# Control_Stage.net
KiCad netlist of a schematic drawn in Altium Designer
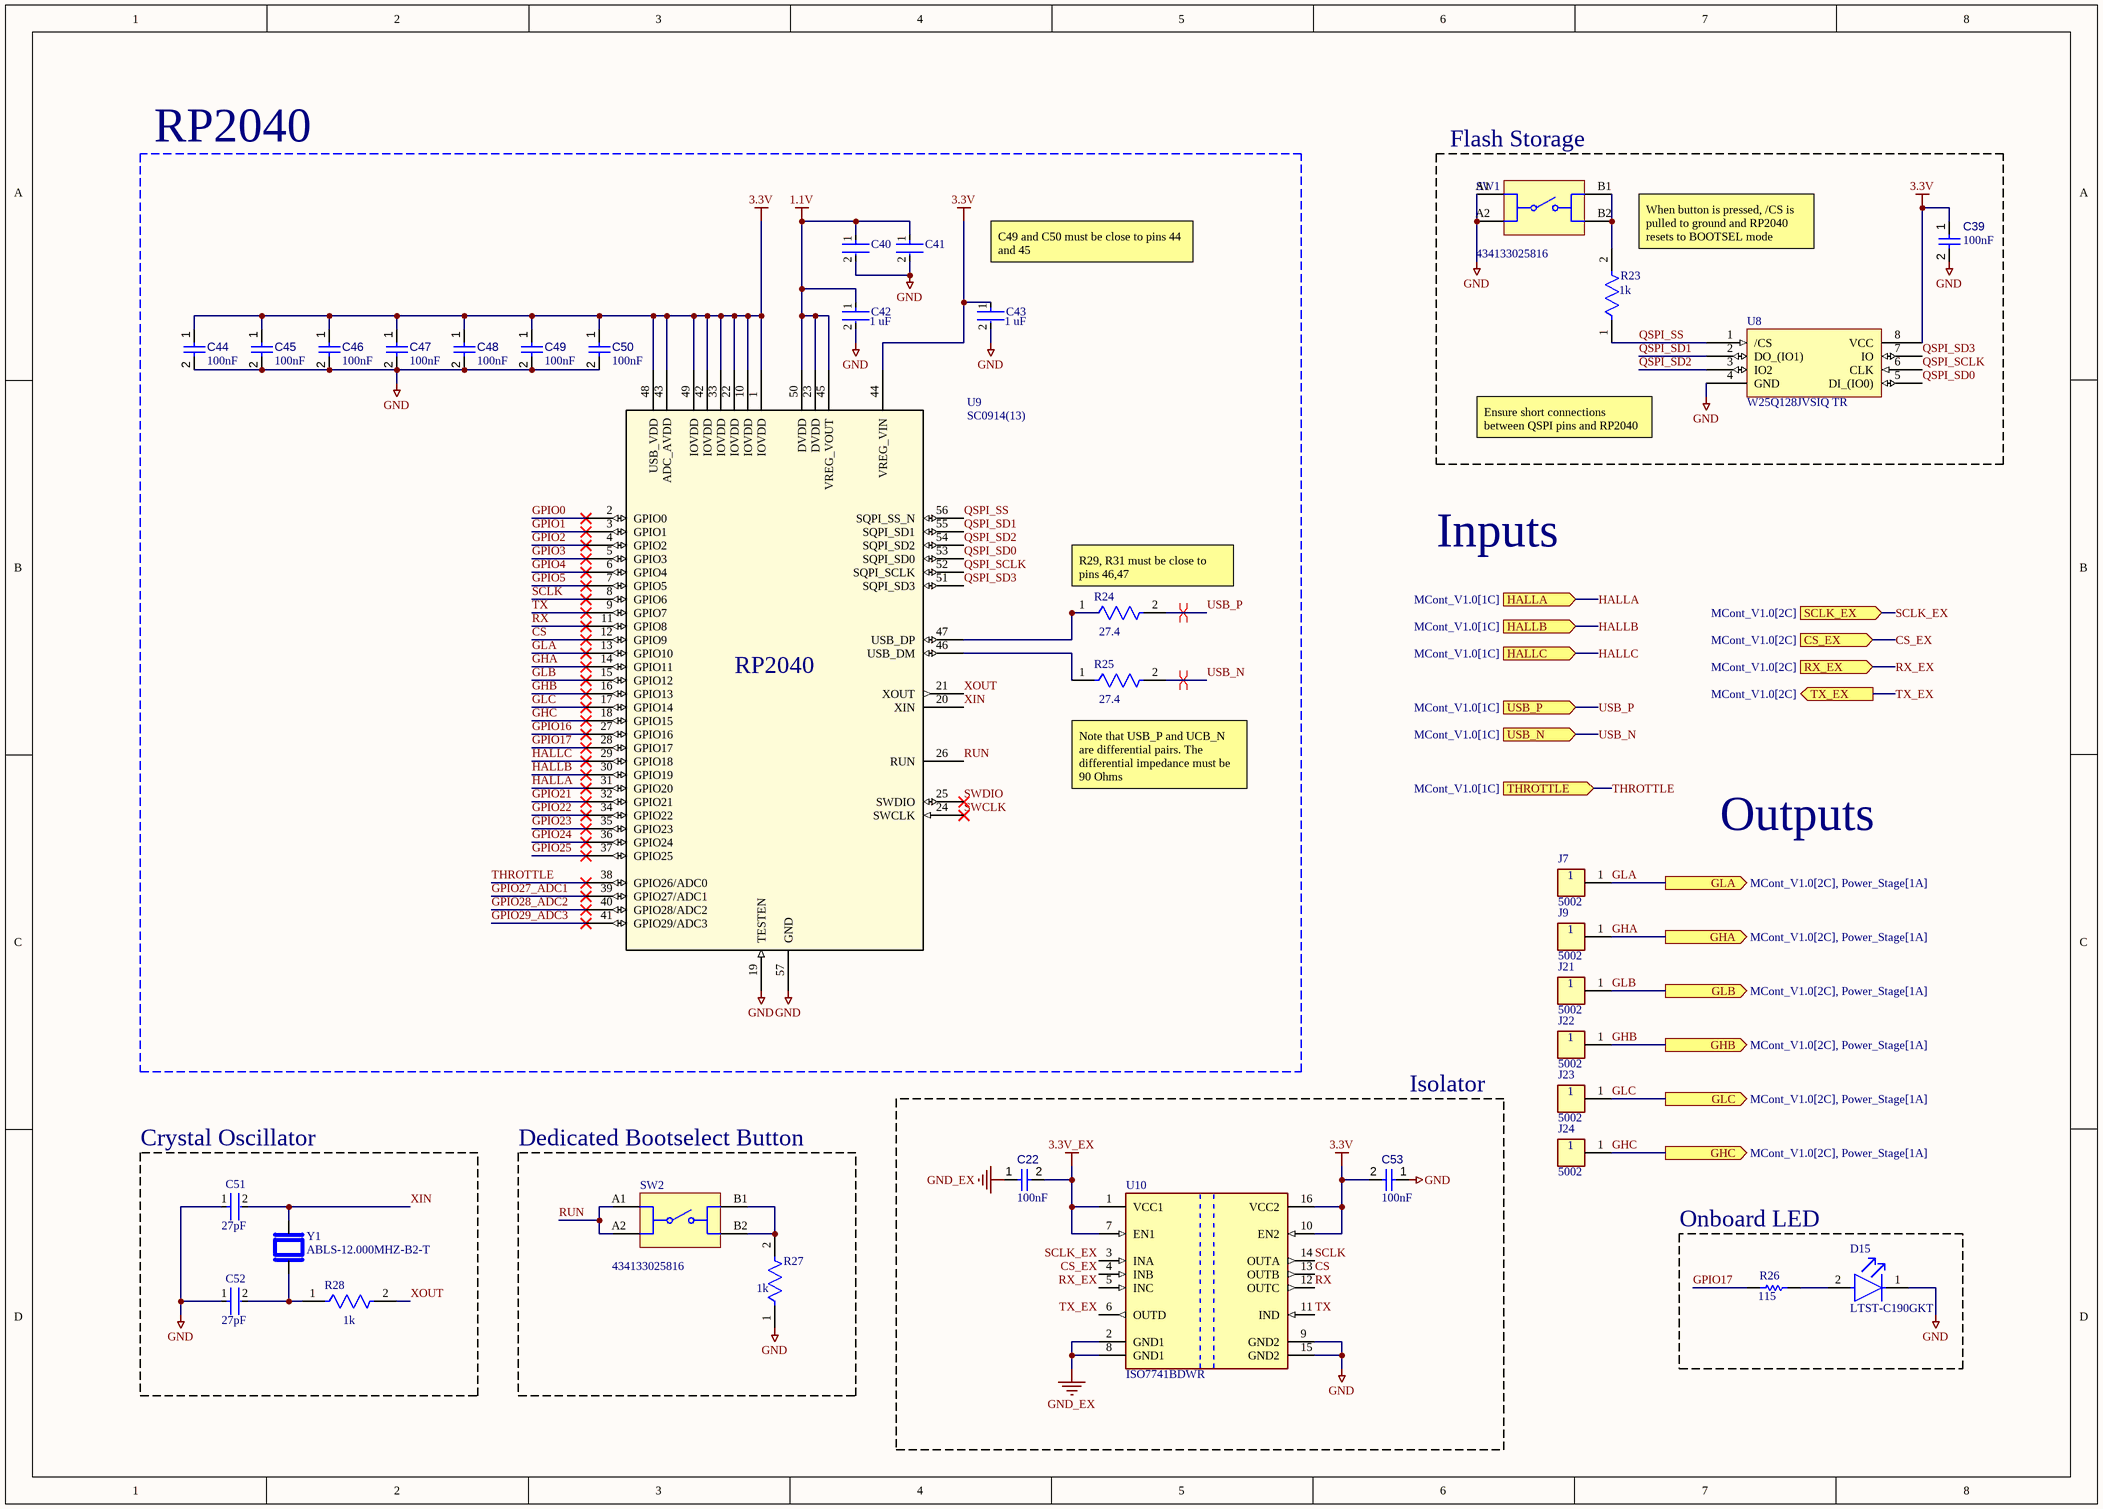
[diagram p0: Control_Stage.SchDoc]

(export (version "E")
  (design (tool "Eeschema 10.0.6"))
  (components
    (comp (ref "C22")
      (value "100nF")
      (footprint "FP-CL10-IPC_B")
      (fields (field (name "Comment") "CL10B104KC8NNNC"))
      (libsource (lib "CEV Electrical") (part "CAP-NP-2"))
    )
    (comp (ref "C39")
      (value "100nF")
      (footprint "FP-CL10-IPC_B")
      (fields (field (name "Comment") "CL10B104KC8NNNC"))
      (libsource (lib "CEV Electrical") (part "CAP-NP-2"))
    )
    (comp (ref "C40")
      (value "CL10B104KC8NNNC")
      (footprint "FP-CL10-IPC_A")
      (description "Cap Ceramic 100nF 100V X7R ±10% Pad SMD 0603 +125°C T/R")
      (fields (field (name "TOLERANCE") "10%"))
      (libsource (lib "Altium Content Vault") (part "b4654b650e69147ec39a6b967a45e02"))
    )
    (comp (ref "C41")
      (value "CL10B104KC8NNNC")
      (footprint "FP-CL10-IPC_A")
      (description "Cap Ceramic 100nF 100V X7R ±10% Pad SMD 0603 +125°C T/R")
      (fields (field (name "TOLERANCE") "10%"))
      (libsource (lib "Altium Content Vault") (part "b4654b650e69147ec39a6b967a45e02"))
    )
    (comp (ref "C42")
      (value "UMK107AB7105KA-T")
      (footprint "FP-0603-L_1_6_0_15-W_0_8-IPC_C")
      (description "Ceramic Capacitor General Use 1uF ±10% 50V X7R 0603")
      (fields (field (name "TOLERANCE") "10%"))
      (libsource (lib "Altium Content Vault") (part "11868f565c42a9108669ba33697ecf6"))
    )
    (comp (ref "C43")
      (value "UMK107AB7105KA-T")
      (footprint "FP-0603-L_1_6_0_15-W_0_8-IPC_C")
      (description "Ceramic Capacitor General Use 1uF ±10% 50V X7R 0603")
      (fields (field (name "TOLERANCE") "10%"))
      (libsource (lib "Altium Content Vault") (part "11868f565c42a9108669ba33697ecf6"))
    )
    (comp (ref "C44")
      (value "100nF")
      (footprint "FP-CL10-IPC_B")
      (fields (field (name "Comment") "CL10B104KC8NNNC"))
      (libsource (lib "CEV Electrical") (part "CAP-NP-2"))
    )
    (comp (ref "C45")
      (value "100nF")
      (footprint "FP-CL10-IPC_B")
      (fields (field (name "Comment") "CL10B104KC8NNNC"))
      (libsource (lib "CEV Electrical") (part "CAP-NP-2"))
    )
    (comp (ref "C46")
      (value "100nF")
      (footprint "FP-CL10-IPC_B")
      (fields (field (name "Comment") "CL10B104KC8NNNC"))
      (libsource (lib "CEV Electrical") (part "CAP-NP-2"))
    )
    (comp (ref "C47")
      (value "100nF")
      (footprint "FP-CL10-IPC_B")
      (fields (field (name "Comment") "CL10B104KC8NNNC"))
      (libsource (lib "CEV Electrical") (part "CAP-NP-2"))
    )
    (comp (ref "C48")
      (value "100nF")
      (footprint "FP-CL10-IPC_B")
      (fields (field (name "Comment") "CL10B104KC8NNNC"))
      (libsource (lib "CEV Electrical") (part "CAP-NP-2"))
    )
    (comp (ref "C49")
      (value "100nF")
      (footprint "FP-CL10-IPC_B")
      (fields (field (name "Comment") "CL10B104KC8NNNC"))
      (libsource (lib "CEV Electrical") (part "CAP-NP-2"))
    )
    (comp (ref "C50")
      (value "100nF")
      (footprint "FP-CL10-IPC_B")
      (fields (field (name "Comment") "CL10B104KC8NNNC"))
      (libsource (lib "CEV Electrical") (part "CAP-NP-2"))
    )
    (comp (ref "C51")
      (value "C0603C270J5GACTU")
      (footprint "FP-C0603C-CF-MFG")
      (description "CAP CER 27PF 50V C0G/NP0 0603")
      (fields
        (field (name "TOLERANCE") "0.05")
        (field (name "OCTOPART") "https://octopart.com/c0603c270j5gactu-kemet-136059")
      )
      (libsource (lib "Altium Content Vault") (part "b4654b650e69147ec39a6b967a45e02"))
    )
    (comp (ref "C52")
      (value "C0603C270J5GACTU")
      (footprint "FP-C0603C-CF-MFG")
      (description "CAP CER 27PF 50V C0G/NP0 0603")
      (fields
        (field (name "TOLERANCE") "0.05")
        (field (name "OCTOPART") "https://octopart.com/c0603c270j5gactu-kemet-136059")
      )
      (libsource (lib "Altium Content Vault") (part "b4654b650e69147ec39a6b967a45e02"))
    )
    (comp (ref "C53")
      (value "100nF")
      (footprint "FP-CL10-IPC_B")
      (fields (field (name "Comment") "CL10B104KC8NNNC"))
      (libsource (lib "CEV Electrical") (part "CAP-NP-2"))
    )
    (comp (ref "D15")
      (value "LTST-C190GKT")
      (footprint "FP-LTST-C190GKT-MFG")
      (description "LED GREEN CLEAR CHIP SMD")
      (fields (field (name "VOLTAGE") "2V"))
      (libsource (lib "Altium Content Vault") (part "8706943c75ba83719d021d2fdc84c58"))
    )
    (comp (ref "J7")
      (value "5002")
      (footprint "FP-5002-MFG")
      (description "PC TEST POINT MINIATURE WHITE")
      (libsource (lib "Altium Content Vault") (part "1e4615820a309e3ce90f9e6d957b7fa"))
    )
    (comp (ref "J9")
      (value "5002")
      (footprint "FP-5002-MFG")
      (description "PC TEST POINT MINIATURE WHITE")
      (libsource (lib "Altium Content Vault") (part "1e4615820a309e3ce90f9e6d957b7fa"))
    )
    (comp (ref "J21")
      (value "5002")
      (footprint "FP-5002-MFG")
      (description "PC TEST POINT MINIATURE WHITE")
      (libsource (lib "Altium Content Vault") (part "1e4615820a309e3ce90f9e6d957b7fa"))
    )
    (comp (ref "J22")
      (value "5002")
      (footprint "FP-5002-MFG")
      (description "PC TEST POINT MINIATURE WHITE")
      (libsource (lib "Altium Content Vault") (part "1e4615820a309e3ce90f9e6d957b7fa"))
    )
    (comp (ref "J23")
      (value "5002")
      (footprint "FP-5002-MFG")
      (description "PC TEST POINT MINIATURE WHITE")
      (libsource (lib "Altium Content Vault") (part "1e4615820a309e3ce90f9e6d957b7fa"))
    )
    (comp (ref "J24")
      (value "5002")
      (footprint "FP-5002-MFG")
      (description "PC TEST POINT MINIATURE WHITE")
      (libsource (lib "Altium Content Vault") (part "1e4615820a309e3ce90f9e6d957b7fa"))
    )
    (comp (ref "R23")
      (value "RC0603FR-071KL")
      (footprint "FP-RC0603-0_55-IPC_C")
      (description "RES 1K OHM 1% 1/10W 0603")
      (fields (field (name "TOLERANCE") "1%"))
      (libsource (lib "Altium Content Vault") (part "1029c3af85768c4190bb7ad29bc67b5"))
    )
    (comp (ref "R24")
      (value "CRCW060327R4FKEA")
      (footprint "FP-CRCW0603-e3-MFG")
      (description "RES Thick Film, 27.4Ω, 1%, 0.1W, 100ppm/°C, 0603")
      (fields (field (name "TOLERANCE") "1%"))
      (libsource (lib "Altium Content Vault") (part "1029c3af85768c4190bb7ad29bc67b5"))
    )
    (comp (ref "R25")
      (value "CRCW060327R4FKEA")
      (footprint "FP-CRCW0603-e3-MFG")
      (description "RES Thick Film, 27.4Ω, 1%, 0.1W, 100ppm/°C, 0603")
      (fields (field (name "TOLERANCE") "1%"))
      (libsource (lib "Altium Content Vault") (part "1029c3af85768c4190bb7ad29bc67b5"))
    )
    (comp (ref "R26")
      (value "ERJ-3EKF1150V")
      (footprint "RESC1608X55X30NL15T15")
      (fields (field (name "MANUFACTURER") "Panasonic"))
      (libsource (lib "Altium Content Vault") (part "RES"))
    )
    (comp (ref "R27")
      (value "RC0603FR-071KL")
      (footprint "FP-RC0603-0_55-IPC_C")
      (description "RES 1K OHM 1% 1/10W 0603")
      (fields (field (name "TOLERANCE") "1%"))
      (libsource (lib "Altium Content Vault") (part "1029c3af85768c4190bb7ad29bc67b5"))
    )
    (comp (ref "R28")
      (value "RC0603FR-071KL")
      (footprint "FP-RC0603-0_55-IPC_C")
      (description "RES 1K OHM 1% 1/10W 0603")
      (fields (field (name "TOLERANCE") "1%"))
      (libsource (lib "Altium Content Vault") (part "1029c3af85768c4190bb7ad29bc67b5"))
    )
    (comp (ref "SW1")
      (value "434133025816")
      (footprint "434133025816")
      (description "Tactile Switch, 0.05A, 16Vdc, 160Gf, Smd Rohs Compliant: Yes")
      (libsource (lib "Altium Content Vault") (part "SPST-NO_4P"))
    )
    (comp (ref "SW2")
      (value "434133025816")
      (footprint "434133025816")
      (description "Tactile Switch, 0.05A, 16Vdc, 160Gf, Smd Rohs Compliant: Yes")
      (libsource (lib "Altium Content Vault") (part "SPST-NO_4P"))
    )
    (comp (ref "U8")
      (value "W25Q128JVSIQ TR")
      (footprint "W25Q128JVSIQ TR-Footprint-1")
      (description "NOR Flash Serial (SPI, Dual SPI, Quad SPI) 3V/3.3V 128M-bit 16M x 8 6ns 8-Pin SOIC T/R")
      (libsource (lib "CEV Electrical New") (part "W25Q128JVSIQ TR-Symbol-1"))
    )
    (comp (ref "U9")
      (value "SC0914(13)")
      (footprint "SC0914(13)-Footprint-1")
      (description "RISC Microcontroller, FLASH, Cortex-M0+ CPU, 133MHz, CMOS")
      (libsource (lib "CEV Electrical New") (part "SC0914(13)-Symbol-1"))
    )
    (comp (ref "U10")
      (value "ISO7741BDWR")
      (footprint "FP-DW0016A-IPC_A")
      (description "DIG ISO - MYNA - QUAD")
      (libsource (lib "Altium Content Vault") (part "66022d5b456763423f468824eb3e28a"))
    )
    (comp (ref "Y1")
      (value "ABLS-12.000MHZ-B2-T")
      (footprint "XTAL_ABLS-12.000MHZ-B2-T")
      (description "Crystal 12MHz ±20ppm (Tol) ±50ppm (Stability) 18pF FUND 50Ohm 2-Pin HC-49/US SMD T/R")
      (fields (field (name "TOLERANCE") "0.002%"))
      (libsource (lib "CEV Electrical New") (part "ABLS-12.000MHZ-B2-T"))
    )
  )
  (nets
    (net (code "1") (name "/CS") (class "Default")
      (node (ref "U10") (pin "13") (pinfunction "OUTB_13") (pintype "output"))
      (node (ref "U9") (pin "12") (pinfunction "GPIO9_12") (pintype "bidirectional"))
    )
    (net (code "2") (name "/CS_EX") (class "Default")
      (node (ref "U10") (pin "4") (pinfunction "INB_4") (pintype "input"))
    )
    (net (code "3") (name "/GHA") (class "Default")
      (node (ref "J9") (pin "1") (pinfunction "1_1") (pintype "passive"))
      (node (ref "U9") (pin "14") (pinfunction "GPIO11_14") (pintype "bidirectional"))
    )
    (net (code "4") (name "/GHB") (class "Default")
      (node (ref "J22") (pin "1") (pinfunction "1_1") (pintype "passive"))
      (node (ref "U9") (pin "16") (pinfunction "GPIO13_16") (pintype "bidirectional"))
    )
    (net (code "5") (name "/GHC") (class "Default")
      (node (ref "J24") (pin "1") (pinfunction "1_1") (pintype "passive"))
      (node (ref "U9") (pin "18") (pinfunction "GPIO15_18") (pintype "bidirectional"))
    )
    (net (code "6") (name "/GLA") (class "Default")
      (node (ref "J7") (pin "1") (pinfunction "1_1") (pintype "passive"))
      (node (ref "U9") (pin "13") (pinfunction "GPIO10_13") (pintype "bidirectional"))
    )
    (net (code "7") (name "/GLB") (class "Default")
      (node (ref "J21") (pin "1") (pinfunction "1_1") (pintype "passive"))
      (node (ref "U9") (pin "15") (pinfunction "GPIO12_15") (pintype "bidirectional"))
    )
    (net (code "8") (name "/GLC") (class "Default")
      (node (ref "J23") (pin "1") (pinfunction "1_1") (pintype "passive"))
      (node (ref "U9") (pin "17") (pinfunction "GPIO14_17") (pintype "bidirectional"))
    )
    (net (code "9") (name "/GPIO0") (class "Default")
      (node (ref "U9") (pin "2") (pinfunction "GPIO0_2") (pintype "bidirectional+no_connect"))
    )
    (net (code "10") (name "/GPIO1") (class "Default")
      (node (ref "U9") (pin "3") (pinfunction "GPIO1_3") (pintype "bidirectional+no_connect"))
    )
    (net (code "11") (name "/GPIO2") (class "Default")
      (node (ref "U9") (pin "4") (pinfunction "GPIO2_4") (pintype "bidirectional+no_connect"))
    )
    (net (code "12") (name "/GPIO3") (class "Default")
      (node (ref "U9") (pin "5") (pinfunction "GPIO3_5") (pintype "bidirectional+no_connect"))
    )
    (net (code "13") (name "/GPIO4") (class "Default")
      (node (ref "U9") (pin "6") (pinfunction "GPIO4_6") (pintype "bidirectional+no_connect"))
    )
    (net (code "14") (name "/GPIO5") (class "Default")
      (node (ref "U9") (pin "7") (pinfunction "GPIO5_7") (pintype "bidirectional+no_connect"))
    )
    (net (code "15") (name "/GPIO16") (class "Default")
      (node (ref "U9") (pin "27") (pinfunction "GPIO16_27") (pintype "bidirectional+no_connect"))
    )
    (net (code "16") (name "/GPIO17") (class "Default")
      (node (ref "R26") (pin "1") (pinfunction "1_1") (pintype "passive"))
      (node (ref "U9") (pin "28") (pinfunction "GPIO17_28") (pintype "bidirectional"))
    )
    (net (code "17") (name "/GPIO21") (class "Default")
      (node (ref "U9") (pin "32") (pinfunction "GPIO21_32") (pintype "bidirectional+no_connect"))
    )
    (net (code "18") (name "/GPIO22") (class "Default")
      (node (ref "U9") (pin "34") (pinfunction "GPIO22_34") (pintype "bidirectional+no_connect"))
    )
    (net (code "19") (name "/GPIO23") (class "Default")
      (node (ref "U9") (pin "35") (pinfunction "GPIO23_35") (pintype "bidirectional+no_connect"))
    )
    (net (code "20") (name "/GPIO24") (class "Default")
      (node (ref "U9") (pin "36") (pinfunction "GPIO24_36") (pintype "bidirectional+no_connect"))
    )
    (net (code "21") (name "/GPIO25") (class "Default")
      (node (ref "U9") (pin "37") (pinfunction "GPIO25_37") (pintype "bidirectional+no_connect"))
    )
    (net (code "22") (name "/GPIO27_ADC1") (class "Default")
      (node (ref "U9") (pin "39") (pinfunction "GPIO27/ADC1_39") (pintype "bidirectional+no_connect"))
    )
    (net (code "23") (name "/GPIO28_ADC2") (class "Default")
      (node (ref "U9") (pin "40") (pinfunction "GPIO28/ADC2_40") (pintype "bidirectional+no_connect"))
    )
    (net (code "24") (name "/GPIO29_ADC3") (class "Default")
      (node (ref "U9") (pin "41") (pinfunction "GPIO29/ADC3_41") (pintype "bidirectional+no_connect"))
    )
    (net (code "25") (name "/HALLA") (class "Default")
      (node (ref "U9") (pin "31") (pinfunction "GPIO20_31") (pintype "bidirectional+no_connect"))
    )
    (net (code "26") (name "/HALLB") (class "Default")
      (node (ref "U9") (pin "30") (pinfunction "GPIO19_30") (pintype "bidirectional+no_connect"))
    )
    (net (code "27") (name "/HALLC") (class "Default")
      (node (ref "U9") (pin "29") (pinfunction "GPIO18_29") (pintype "bidirectional+no_connect"))
    )
    (net (code "28") (name "/QSPI_SCLK") (class "Default")
      (node (ref "U8") (pin "6") (pinfunction "CLK_6") (pintype "input"))
      (node (ref "U9") (pin "52") (pinfunction "SQPI_SCLK_52") (pintype "bidirectional"))
    )
    (net (code "29") (name "/QSPI_SD0") (class "Default")
      (node (ref "U8") (pin "5") (pinfunction "DI_(IO0)_5") (pintype "bidirectional"))
      (node (ref "U9") (pin "53") (pinfunction "SQPI_SD0_53") (pintype "bidirectional"))
    )
    (net (code "30") (name "/QSPI_SD1") (class "Default")
      (node (ref "U8") (pin "2") (pinfunction "DO_(IO1)_2") (pintype "bidirectional"))
      (node (ref "U9") (pin "55") (pinfunction "SQPI_SD1_55") (pintype "bidirectional"))
    )
    (net (code "31") (name "/QSPI_SD2") (class "Default")
      (node (ref "U8") (pin "3") (pinfunction "IO2_3") (pintype "bidirectional"))
      (node (ref "U9") (pin "54") (pinfunction "SQPI_SD2_54") (pintype "bidirectional"))
    )
    (net (code "32") (name "/QSPI_SD3") (class "Default")
      (node (ref "U8") (pin "7") (pinfunction "IO_7") (pintype "bidirectional"))
      (node (ref "U9") (pin "51") (pinfunction "SQPI_SD3_51") (pintype "bidirectional"))
    )
    (net (code "33") (name "/QSPI_SS") (class "Default")
      (node (ref "R23") (pin "1") (pinfunction "1_1") (pintype "passive"))
      (node (ref "U8") (pin "1") (pinfunction "/CS_1") (pintype "input"))
      (node (ref "U9") (pin "56") (pinfunction "SQPI_SS_N_56") (pintype "bidirectional"))
    )
    (net (code "34") (name "/RUN") (class "Default")
      (node (ref "SW2") (pin "A1") (pinfunction "A1_A1") (pintype "passive"))
      (node (ref "SW2") (pin "A2") (pinfunction "A2_A2") (pintype "passive"))
      (node (ref "U9") (pin "26") (pinfunction "RUN_26") (pintype "passive"))
    )
    (net (code "35") (name "/RX") (class "Default")
      (node (ref "U10") (pin "12") (pinfunction "OUTC_12") (pintype "output"))
      (node (ref "U9") (pin "11") (pinfunction "GPIO8_11") (pintype "bidirectional"))
    )
    (net (code "36") (name "/RX_EX") (class "Default")
      (node (ref "U10") (pin "5") (pinfunction "INC_5") (pintype "input"))
    )
    (net (code "37") (name "/SCLK") (class "Default")
      (node (ref "U10") (pin "14") (pinfunction "OUTA_14") (pintype "output"))
      (node (ref "U9") (pin "8") (pinfunction "GPIO6_8") (pintype "bidirectional"))
    )
    (net (code "38") (name "/SCLK_EX") (class "Default")
      (node (ref "U10") (pin "3") (pinfunction "INA_3") (pintype "input"))
    )
    (net (code "39") (name "/SWCLK") (class "Default")
      (node (ref "U9") (pin "24") (pinfunction "SWCLK_24") (pintype "input+no_connect"))
    )
    (net (code "40") (name "/SWDIO") (class "Default")
      (node (ref "U9") (pin "25") (pinfunction "SWDIO_25") (pintype "bidirectional+no_connect"))
    )
    (net (code "41") (name "/THROTTLE") (class "Default")
      (node (ref "U9") (pin "38") (pinfunction "GPIO26/ADC0_38") (pintype "bidirectional"))
    )
    (net (code "42") (name "/TX") (class "Default")
      (node (ref "U10") (pin "11") (pinfunction "IND_11") (pintype "input"))
      (node (ref "U9") (pin "9") (pinfunction "GPIO7_9") (pintype "bidirectional"))
    )
    (net (code "43") (name "/TX_EX") (class "Default")
      (node (ref "U10") (pin "6") (pinfunction "OUTD_6") (pintype "output"))
    )
    (net (code "44") (name "/USB_N") (class "Default")
      (node (ref "R25") (pin "2") (pinfunction "2_2") (pintype "passive"))
    )
    (net (code "45") (name "/USB_P") (class "Default")
      (node (ref "R24") (pin "2") (pinfunction "2_2") (pintype "passive"))
    )
    (net (code "46") (name "/XIN") (class "Default")
      (node (ref "C51") (pin "2") (pinfunction "2_2") (pintype "passive"))
      (node (ref "U9") (pin "20") (pinfunction "XIN_20") (pintype "passive"))
      (node (ref "Y1") (pin "2") (pinfunction "2_2") (pintype "passive"))
    )
    (net (code "47") (name "/XOUT") (class "Default")
      (node (ref "R28") (pin "2") (pinfunction "2_2") (pintype "passive"))
      (node (ref "U9") (pin "21") (pinfunction "XOUT_21") (pintype "output"))
    )
    (net (code "48") (name "1.1V") (class "Default")
      (node (ref "C40") (pin "1") (pinfunction "1_1") (pintype "passive"))
      (node (ref "C41") (pin "1") (pinfunction "1_1") (pintype "passive"))
      (node (ref "C42") (pin "1") (pinfunction "1_1") (pintype "passive"))
      (node (ref "U9") (pin "23") (pinfunction "DVDD_23") (pintype "power_in"))
      (node (ref "U9") (pin "45") (pinfunction "VREG_VOUT_45") (pintype "power_in"))
      (node (ref "U9") (pin "50") (pinfunction "DVDD_50") (pintype "power_in"))
    )
    (net (code "49") (name "3.3V") (class "Default")
      (node (ref "C39") (pin "1") (pinfunction "1_1") (pintype "passive"))
      (node (ref "C43") (pin "1") (pinfunction "1_1") (pintype "passive"))
      (node (ref "C44") (pin "1") (pinfunction "1_1") (pintype "passive"))
      (node (ref "C45") (pin "1") (pinfunction "1_1") (pintype "passive"))
      (node (ref "C46") (pin "1") (pinfunction "1_1") (pintype "passive"))
      (node (ref "C47") (pin "1") (pinfunction "1_1") (pintype "passive"))
      (node (ref "C48") (pin "1") (pinfunction "1_1") (pintype "passive"))
      (node (ref "C49") (pin "1") (pinfunction "1_1") (pintype "passive"))
      (node (ref "C50") (pin "1") (pinfunction "1_1") (pintype "passive"))
      (node (ref "C53") (pin "2") (pinfunction "2_2") (pintype "passive"))
      (node (ref "U10") (pin "10") (pinfunction "EN2_10") (pintype "input"))
      (node (ref "U10") (pin "16") (pinfunction "VCC2_16") (pintype "power_in"))
      (node (ref "U8") (pin "8") (pinfunction "VCC_8") (pintype "power_in"))
      (node (ref "U9") (pin "1") (pinfunction "IOVDD_1") (pintype "power_in"))
      (node (ref "U9") (pin "10") (pinfunction "IOVDD_10") (pintype "power_in"))
      (node (ref "U9") (pin "22") (pinfunction "IOVDD_22") (pintype "power_in"))
      (node (ref "U9") (pin "33") (pinfunction "IOVDD_33") (pintype "power_in"))
      (node (ref "U9") (pin "42") (pinfunction "IOVDD_42") (pintype "power_in"))
      (node (ref "U9") (pin "43") (pinfunction "ADC_AVDD_43") (pintype "power_in"))
      (node (ref "U9") (pin "44") (pinfunction "VREG_VIN_44") (pintype "power_in"))
      (node (ref "U9") (pin "48") (pinfunction "USB_VDD_48") (pintype "power_in"))
      (node (ref "U9") (pin "49") (pinfunction "IOVDD_49") (pintype "power_in"))
    )
    (net (code "50") (name "3.3V_EX") (class "Default")
      (node (ref "C22") (pin "2") (pinfunction "2_2") (pintype "passive"))
      (node (ref "U10") (pin "1") (pinfunction "VCC1_1") (pintype "power_in"))
      (node (ref "U10") (pin "7") (pinfunction "EN1_7") (pintype "input"))
    )
    (net (code "51") (name "GND") (class "Default")
      (node (ref "C39") (pin "2") (pinfunction "2_2") (pintype "passive"))
      (node (ref "C40") (pin "2") (pinfunction "2_2") (pintype "passive"))
      (node (ref "C41") (pin "2") (pinfunction "2_2") (pintype "passive"))
      (node (ref "C42") (pin "2") (pinfunction "2_2") (pintype "passive"))
      (node (ref "C43") (pin "2") (pinfunction "2_2") (pintype "passive"))
      (node (ref "C44") (pin "2") (pinfunction "2_2") (pintype "passive"))
      (node (ref "C45") (pin "2") (pinfunction "2_2") (pintype "passive"))
      (node (ref "C46") (pin "2") (pinfunction "2_2") (pintype "passive"))
      (node (ref "C47") (pin "2") (pinfunction "2_2") (pintype "passive"))
      (node (ref "C48") (pin "2") (pinfunction "2_2") (pintype "passive"))
      (node (ref "C49") (pin "2") (pinfunction "2_2") (pintype "passive"))
      (node (ref "C50") (pin "2") (pinfunction "2_2") (pintype "passive"))
      (node (ref "C51") (pin "1") (pinfunction "1_1") (pintype "passive"))
      (node (ref "C52") (pin "1") (pinfunction "1_1") (pintype "passive"))
      (node (ref "C53") (pin "1") (pinfunction "1_1") (pintype "passive"))
      (node (ref "D15") (pin "1") (pinfunction "C_1") (pintype "passive"))
      (node (ref "R27") (pin "1") (pinfunction "1_1") (pintype "passive"))
      (node (ref "SW1") (pin "A1") (pinfunction "A1_A1") (pintype "passive"))
      (node (ref "SW1") (pin "A2") (pinfunction "A2_A2") (pintype "passive"))
      (node (ref "U10") (pin "15") (pinfunction "GND2_15") (pintype "power_in"))
      (node (ref "U10") (pin "9") (pinfunction "GND2_9") (pintype "power_in"))
      (node (ref "U8") (pin "4") (pinfunction "GND_4") (pintype "power_in"))
      (node (ref "U9") (pin "19") (pinfunction "TESTEN_19") (pintype "input"))
      (node (ref "U9") (pin "57") (pinfunction "GND_57") (pintype "power_in"))
    )
    (net (code "52") (name "GND_EX") (class "Default")
      (node (ref "C22") (pin "1") (pinfunction "1_1") (pintype "passive"))
      (node (ref "U10") (pin "2") (pinfunction "GND1_2") (pintype "power_in"))
      (node (ref "U10") (pin "8") (pinfunction "GND1_8") (pintype "power_in"))
    )
    (net (code "53") (name "Net-(C52-Pad2)") (class "Default")
      (node (ref "C52") (pin "2") (pinfunction "2_2") (pintype "passive"))
      (node (ref "R28") (pin "1") (pinfunction "1_1") (pintype "passive"))
      (node (ref "Y1") (pin "1") (pinfunction "1_1") (pintype "passive"))
    )
    (net (code "54") (name "Net-(D15-A)") (class "Default")
      (node (ref "D15") (pin "2") (pinfunction "A_2") (pintype "passive"))
      (node (ref "R26") (pin "2") (pinfunction "2_2") (pintype "passive"))
    )
    (net (code "55") (name "Net-(R23-Pad2)") (class "Default")
      (node (ref "R23") (pin "2") (pinfunction "2_2") (pintype "passive"))
      (node (ref "SW1") (pin "B1") (pinfunction "B1_B1") (pintype "passive"))
      (node (ref "SW1") (pin "B2") (pinfunction "B2_B2") (pintype "passive"))
    )
    (net (code "56") (name "Net-(R27-Pad2)") (class "Default")
      (node (ref "R27") (pin "2") (pinfunction "2_2") (pintype "passive"))
      (node (ref "SW2") (pin "B1") (pinfunction "B1_B1") (pintype "passive"))
      (node (ref "SW2") (pin "B2") (pinfunction "B2_B2") (pintype "passive"))
    )
    (net (code "57") (name "Net-(U9-USB_DM)") (class "Default")
      (node (ref "R25") (pin "1") (pinfunction "1_1") (pintype "passive"))
      (node (ref "U9") (pin "46") (pinfunction "USB_DM_46") (pintype "bidirectional"))
    )
    (net (code "58") (name "Net-(U9-USB_DP)") (class "Default")
      (node (ref "R24") (pin "1") (pinfunction "1_1") (pintype "passive"))
      (node (ref "U9") (pin "47") (pinfunction "USB_DP_47") (pintype "bidirectional"))
    )
  )
)
